# Provisions.net
KiCad netlist of a schematic drawn in Altium Designer
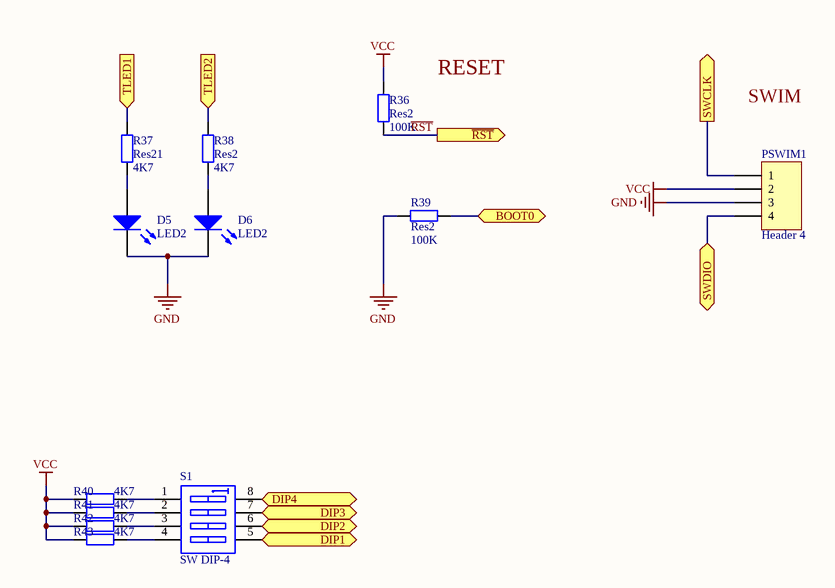
[diagram p0: Provisions.SchDoc]

(export (version "E")
  (design (tool "Eeschema 10.0.6"))
  (components
    (comp (ref "D5")
      (value "LED2")
      (footprint "3.2X1.6X1.1")
      (description "Typical RED, GREEN, YELLOW, AMBER GaAs LED")
      (fields (field (name "PUBLISHER") "Altium Limited"))
      (libsource (lib "Miscellaneous Devices") (part "LED2"))
    )
    (comp (ref "D6")
      (value "LED2")
      (footprint "3.2X1.6X1.1")
      (description "Typical RED, GREEN, YELLOW, AMBER GaAs LED")
      (fields (field (name "PUBLISHER") "Altium Limited"))
      (libsource (lib "Miscellaneous Devices") (part "LED2"))
    )
    (comp (ref "PSWIM1")
      (value "Header 4")
      (footprint "HDR1X4")
      (description "Header, 4-Pin")
      (fields (field (name "PUBLISHER") "Altium Limited"))
      (libsource (lib "Miscellaneous Connectors") (part "Header 4"))
    )
    (comp (ref "R36")
      (value "Res2")
      (footprint "6-0805_N")
      (description "Resistor")
      (fields (field (name "ALTIUM_VALUE") "100K") (field (name "PUBLISHER") "Altium Limited"))
      (libsource (lib "") (part "Res2_1"))
    )
    (comp (ref "R37")
      (value "Res21")
      (footprint "6-0805_N")
      (description "Resistor")
      (fields (field (name "ALTIUM_VALUE") "4K7") (field (name "PUBLISHER") "Altium Limited"))
      (libsource (lib "Miscellaneous Devices") (part "Res21"))
    )
    (comp (ref "R38")
      (value "Res2")
      (footprint "6-0805_N")
      (description "Resistor")
      (fields (field (name "ALTIUM_VALUE") "4K7") (field (name "PUBLISHER") "Altium Limited"))
      (libsource (lib "") (part "Res2_1"))
    )
    (comp (ref "R39")
      (value "Res2")
      (footprint "6-0805_N")
      (description "Resistor")
      (fields (field (name "ALTIUM_VALUE") "100K") (field (name "PUBLISHER") "Altium Limited"))
      (libsource (lib "Miscellaneous Devices") (part "Res2"))
    )
    (comp (ref "R40")
      (value "4K7")
      (footprint "6-0805_N")
      (description "Resistor")
      (fields (field (name "Comment") "Res2") (field (name "PUBLISHER") "Altium Limited"))
      (libsource (lib "Miscellaneous Devices") (part "Res2"))
    )
    (comp (ref "R41")
      (value "4K7")
      (footprint "6-0805_N")
      (description "Resistor")
      (fields (field (name "Comment") "Res2") (field (name "PUBLISHER") "Altium Limited"))
      (libsource (lib "Miscellaneous Devices") (part "Res2"))
    )
    (comp (ref "R42")
      (value "4K7")
      (footprint "6-0805_N")
      (description "Resistor")
      (fields (field (name "Comment") "Res2") (field (name "PUBLISHER") "Altium Limited"))
      (libsource (lib "Miscellaneous Devices") (part "Res2"))
    )
    (comp (ref "R43")
      (value "4K7")
      (footprint "6-0805_N")
      (description "Resistor")
      (fields (field (name "Comment") "Res2") (field (name "PUBLISHER") "Altium Limited"))
      (libsource (lib "Miscellaneous Devices") (part "Res2"))
    )
    (comp (ref "S1")
      (value "SW DIP-4")
      (footprint "SO8_N")
      (description "DIP Switch, 4 Position, SPST")
      (fields (field (name "PUBLISHER") "Altium Limited"))
      (libsource (lib "Miscellaneous Devices") (part "SW DIP-4"))
    )
  )
  (nets
    (net (code "1") (name "/BOOT0") (class "Default")
      (node (ref "R39") (pin "1") (pinfunction "1_1") (pintype "passive"))
    )
    (net (code "2") (name "/DIP1") (class "Default")
      (node (ref "S1") (pin "5") (pinfunction "B4_5") (pintype "passive"))
    )
    (net (code "3") (name "/DIP2") (class "Default")
      (node (ref "S1") (pin "6") (pinfunction "B3_6") (pintype "passive"))
    )
    (net (code "4") (name "/DIP3") (class "Default")
      (node (ref "S1") (pin "7") (pinfunction "B2_7") (pintype "passive"))
    )
    (net (code "5") (name "/DIP4") (class "Default")
      (node (ref "S1") (pin "8") (pinfunction "B1_8") (pintype "passive"))
    )
    (net (code "6") (name "/SWCLK") (class "Default")
      (node (ref "PSWIM1") (pin "1") (pinfunction "1_1") (pintype "passive"))
    )
    (net (code "7") (name "/SWDIO") (class "Default")
      (node (ref "PSWIM1") (pin "4") (pinfunction "4_4") (pintype "passive"))
    )
    (net (code "8") (name "/TLED1") (class "Default")
      (node (ref "R37") (pin "2") (pinfunction "2_2") (pintype "passive"))
    )
    (net (code "9") (name "/TLED2") (class "Default")
      (node (ref "R38") (pin "2") (pinfunction "2_2") (pintype "passive"))
    )
    (net (code "10") (name "/~{RST}") (class "Default")
      (node (ref "R36") (pin "1") (pinfunction "1_1") (pintype "passive"))
    )
    (net (code "11") (name "GND") (class "Default")
      (node (ref "D5") (pin "2") (pinfunction "K_2") (pintype "passive"))
      (node (ref "D6") (pin "2") (pinfunction "K_2") (pintype "passive"))
      (node (ref "PSWIM1") (pin "3") (pinfunction "3_3") (pintype "passive"))
      (node (ref "R39") (pin "2") (pinfunction "2_2") (pintype "passive"))
    )
    (net (code "12") (name "Net-(D5-A)") (class "Default")
      (node (ref "D5") (pin "1") (pinfunction "A_1") (pintype "passive"))
      (node (ref "R37") (pin "1") (pinfunction "1_1") (pintype "passive"))
    )
    (net (code "13") (name "Net-(D6-A)") (class "Default")
      (node (ref "D6") (pin "1") (pinfunction "A_1") (pintype "passive"))
      (node (ref "R38") (pin "1") (pinfunction "1_1") (pintype "passive"))
    )
    (net (code "14") (name "Net-(S1-A1)") (class "Default")
      (node (ref "R40") (pin "1") (pinfunction "1_1") (pintype "passive"))
      (node (ref "S1") (pin "1") (pinfunction "A1_1") (pintype "passive"))
    )
    (net (code "15") (name "Net-(S1-A2)") (class "Default")
      (node (ref "R41") (pin "1") (pinfunction "1_1") (pintype "passive"))
      (node (ref "S1") (pin "2") (pinfunction "A2_2") (pintype "passive"))
    )
    (net (code "16") (name "Net-(S1-A3)") (class "Default")
      (node (ref "R42") (pin "1") (pinfunction "1_1") (pintype "passive"))
      (node (ref "S1") (pin "3") (pinfunction "A3_3") (pintype "passive"))
    )
    (net (code "17") (name "Net-(S1-A4)") (class "Default")
      (node (ref "R43") (pin "1") (pinfunction "1_1") (pintype "passive"))
      (node (ref "S1") (pin "4") (pinfunction "A4_4") (pintype "passive"))
    )
    (net (code "18") (name "VCC") (class "Default")
      (node (ref "PSWIM1") (pin "2") (pinfunction "2_2") (pintype "passive"))
      (node (ref "R36") (pin "2") (pinfunction "2_2") (pintype "passive"))
      (node (ref "R40") (pin "2") (pinfunction "2_2") (pintype "passive"))
      (node (ref "R41") (pin "2") (pinfunction "2_2") (pintype "passive"))
      (node (ref "R42") (pin "2") (pinfunction "2_2") (pintype "passive"))
      (node (ref "R43") (pin "2") (pinfunction "2_2") (pintype "passive"))
    )
  )
)
